# piezo-preamp-tickler_V3-single-supply-OP.net
KiCad netlist of a schematic drawn in EAGLE
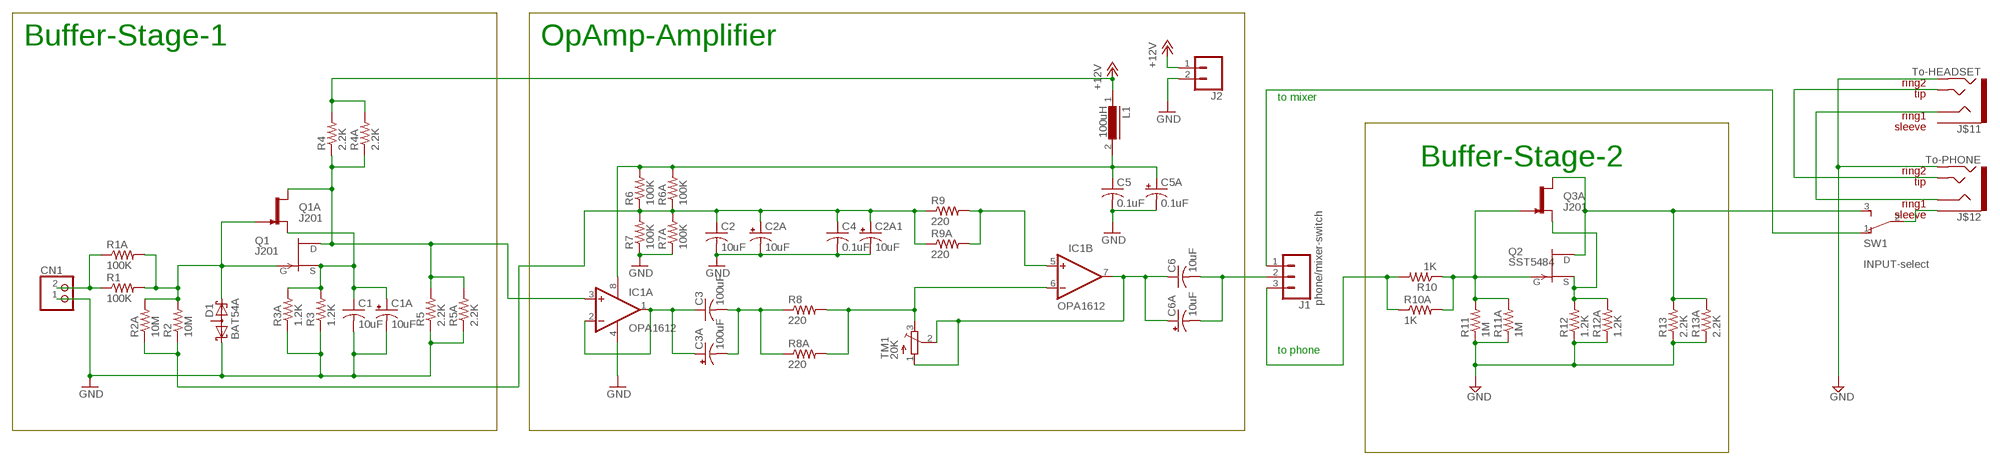
[diagram p0: schematic, sheet 1]
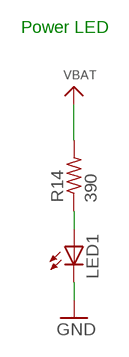
[diagram p1: schematic, sheet 2]

(export (version "E")
  (design (tool "Eeschema 10.0.6"))
  (components
    (comp (ref "C1")
      (value "10uF")
      (footprint "eagle-import:C0805K")
      (libsource (lib "eagle-import") (part "C-USC0805K"))
    )
    (comp (ref "C1A")
      (value "10uF")
      (footprint "eagle-import:E2,5-6E")
      (libsource (lib "eagle-import") (part "CPOL-USE2,5-6E"))
    )
    (comp (ref "C2")
      (value "10uF")
      (footprint "eagle-import:C0805K")
      (libsource (lib "eagle-import") (part "rcl_334_C-USC0805K"))
    )
    (comp (ref "C2A")
      (value "10uF")
      (footprint "eagle-import:E2,5-6E")
      (libsource (lib "eagle-import") (part "CPOL-USE2,5-6E"))
    )
    (comp (ref "C2A1")
      (value "10uF")
      (footprint "eagle-import:E2,5-6E")
      (libsource (lib "eagle-import") (part "CPOL-USE2,5-6E"))
    )
    (comp (ref "C3")
      (value "100uF")
      (footprint "eagle-import:C0805K")
      (libsource (lib "eagle-import") (part "C-USC0805K"))
    )
    (comp (ref "C3A")
      (value "100uF")
      (footprint "eagle-import:E2,5-6E")
      (libsource (lib "eagle-import") (part "CPOL-USE2,5-6E"))
    )
    (comp (ref "C4")
      (value "0.1uF")
      (footprint "eagle-import:C0805K")
      (libsource (lib "eagle-import") (part "C-USC0805K"))
    )
    (comp (ref "C5")
      (value "0.1uF")
      (footprint "eagle-import:C0805K")
      (libsource (lib "eagle-import") (part "C-USC0805K"))
    )
    (comp (ref "C5A")
      (value "0.1uF")
      (footprint "eagle-import:E2,5-6E")
      (libsource (lib "eagle-import") (part "CPOL-USE2,5-6E"))
    )
    (comp (ref "C6")
      (value "10uF")
      (footprint "eagle-import:C0805K")
      (libsource (lib "eagle-import") (part "C-USC0805K"))
    )
    (comp (ref "C6A")
      (value "10uF")
      (footprint "eagle-import:E2,5-6E")
      (libsource (lib "eagle-import") (part "CPOL-USE2,5-6E"))
    )
    (comp (ref "CN1")
      (value "JST_2PIN-THM")
      (footprint "eagle-import:JST-PH-2-THM")
      (libsource (lib "eagle-import") (part "JST_2PIN-THM"))
    )
    (comp (ref "D1")
      (value "BAT54A")
      (footprint "eagle-import:SOT23")
      (libsource (lib "eagle-import") (part "BAT54A"))
    )
    (comp (ref "IC1")
      (value "OPA1612")
      (footprint "eagle-import:SO08")
      (libsource (lib "eagle-import") (part "OPA2UA134"))
    )
    (comp (ref "J$11")
      (value "To-HEADSET")
      (footprint "eagle-import:TRRS-SJ-43514-SMT-TR")
      (libsource (lib "eagle-import") (part "TRRS-3.5MMSJ-43512-SMT"))
    )
    (comp (ref "J$12")
      (value "To-PHONE")
      (footprint "eagle-import:TRRS-SJ-43514-SMT-TR")
      (libsource (lib "eagle-import") (part "TRRS-3.5MMSJ-43512-SMT"))
    )
    (comp (ref "J1")
      (value "phone/mixer-switch")
      (footprint "eagle-import:1X03_LOCK")
      (libsource (lib "eagle-import") (part "CONN_03LOCK"))
    )
    (comp (ref "J2")
      (value "CONN_02LOCK")
      (footprint "eagle-import:1X02_LOCK")
      (libsource (lib "eagle-import") (part "CONN_02LOCK"))
    )
    (comp (ref "L1")
      (value "100uH")
      (footprint "eagle-import:LBC-SE")
      (libsource (lib "eagle-import") (part "LBC-SE"))
    )
    (comp (ref "Q1")
      (value "J201")
      (footprint "eagle-import:SOT23")
      (libsource (lib "eagle-import") (part "?548SST4"))
    )
    (comp (ref "Q1A")
      (value "J201")
      (footprint "eagle-import:TO92-")
      (libsource (lib "eagle-import") (part "J201"))
    )
    (comp (ref "Q2")
      (value "SST5484")
      (footprint "eagle-import:SOT23")
      (libsource (lib "eagle-import") (part "?548SST4"))
    )
    (comp (ref "Q3A")
      (value "J201")
      (footprint "eagle-import:TO92-")
      (libsource (lib "eagle-import") (part "J201"))
    )
    (comp (ref "R1")
      (value "100K")
      (footprint "eagle-import:R0603")
      (libsource (lib "eagle-import") (part "R-US_R0603"))
    )
    (comp (ref "R1A")
      (value "100K")
      (footprint "eagle-import:0204V")
      (libsource (lib "eagle-import") (part "R-US_0204/2V"))
    )
    (comp (ref "R2")
      (value "10M")
      (footprint "eagle-import:R0603")
      (libsource (lib "eagle-import") (part "R-US_R0603"))
    )
    (comp (ref "R2A")
      (value "10M")
      (footprint "eagle-import:0204V")
      (libsource (lib "eagle-import") (part "R-US_0204/2V"))
    )
    (comp (ref "R3")
      (value "1.2K")
      (footprint "eagle-import:R0603")
      (libsource (lib "eagle-import") (part "R-US_R0603"))
    )
    (comp (ref "R3A")
      (value "1.2K")
      (footprint "eagle-import:0204V")
      (libsource (lib "eagle-import") (part "R-US_0204/2V"))
    )
    (comp (ref "R4")
      (value "2.2K")
      (footprint "eagle-import:R0603")
      (libsource (lib "eagle-import") (part "R-US_R0603"))
    )
    (comp (ref "R4A")
      (value "2.2K")
      (footprint "eagle-import:0204V")
      (libsource (lib "eagle-import") (part "R-US_0204/2V"))
    )
    (comp (ref "R5")
      (value "2.2K")
      (footprint "eagle-import:R0603")
      (libsource (lib "eagle-import") (part "R-US_R0603"))
    )
    (comp (ref "R5A")
      (value "2.2K")
      (footprint "eagle-import:0204V")
      (libsource (lib "eagle-import") (part "R-US_0204/2V"))
    )
    (comp (ref "R6")
      (value "100K")
      (footprint "eagle-import:R0603")
      (libsource (lib "eagle-import") (part "R-US_R0603"))
    )
    (comp (ref "R6A")
      (value "100K")
      (footprint "eagle-import:0204V")
      (libsource (lib "eagle-import") (part "R-US_0204/2V"))
    )
    (comp (ref "R7")
      (value "100K")
      (footprint "eagle-import:R0603")
      (libsource (lib "eagle-import") (part "R-US_R0603"))
    )
    (comp (ref "R7A")
      (value "100K")
      (footprint "eagle-import:0204V")
      (libsource (lib "eagle-import") (part "R-US_0204/2V"))
    )
    (comp (ref "R8")
      (value "220")
      (footprint "eagle-import:R0603")
      (libsource (lib "eagle-import") (part "R-US_R0603"))
    )
    (comp (ref "R8A")
      (value "220")
      (footprint "eagle-import:R0603")
      (libsource (lib "eagle-import") (part "R-US_R0603"))
    )
    (comp (ref "R9")
      (value "220")
      (footprint "eagle-import:R0603")
      (libsource (lib "eagle-import") (part "R-US_R0603"))
    )
    (comp (ref "R9A")
      (value "220")
      (footprint "eagle-import:0204V")
      (libsource (lib "eagle-import") (part "R-US_0204/2V"))
    )
    (comp (ref "R10")
      (value "1K")
      (footprint "eagle-import:R0603")
      (libsource (lib "eagle-import") (part "R-US_R0603"))
    )
    (comp (ref "R10A")
      (value "1K")
      (footprint "eagle-import:0204V")
      (libsource (lib "eagle-import") (part "R-US_0204/2V"))
    )
    (comp (ref "R11")
      (value "1M")
      (footprint "eagle-import:R0603")
      (libsource (lib "eagle-import") (part "R-US_R0603"))
    )
    (comp (ref "R11A")
      (value "1M")
      (footprint "eagle-import:0204V")
      (libsource (lib "eagle-import") (part "R-US_0204/2V"))
    )
    (comp (ref "R12")
      (value "1.2K")
      (footprint "eagle-import:R0603")
      (libsource (lib "eagle-import") (part "R-US_R0603"))
    )
    (comp (ref "R12A")
      (value "1.2K")
      (footprint "eagle-import:0204V")
      (libsource (lib "eagle-import") (part "R-US_0204/2V"))
    )
    (comp (ref "R13")
      (value "2.2K")
      (footprint "eagle-import:R0603")
      (libsource (lib "eagle-import") (part "R-US_R0603"))
    )
    (comp (ref "R13A")
      (value "2.2K")
      (footprint "eagle-import:0204V")
      (libsource (lib "eagle-import") (part "R-US_0204/2V"))
    )
    (comp (ref "SW1")
      (value "INPUT-select")
      (footprint "eagle-import:SWITCH_SPDT-TE-CONNECT")
      (libsource (lib "eagle-import") (part "SWITCH_SPDTTE-CONNECT"))
    )
    (comp (ref "TM1")
      (value "20K")
      (footprint "eagle-import:TC33X")
      (libsource (lib "eagle-import") (part "TRIMPOTTC33X"))
    )
    (comp (ref "LED1")
      (value "LED3MM")
      (footprint "eagle-import:LED3MM")
      (libsource (lib "eagle-import") (part "LED3MM"))
    )
    (comp (ref "R14")
      (value "390")
      (footprint "eagle-import:R0805")
      (libsource (lib "eagle-import") (part "R-US_R0805"))
    )
  )
  (nets
    (net (code "1") (name "+12V") (class "Default")
      (node (ref "J2") (pin "1") (pinfunction "1_1") (pintype "passive"))
      (node (ref "L1") (pin "1") (pinfunction "1_1") (pintype "passive"))
      (node (ref "R4") (pin "2") (pinfunction "2_2") (pintype "passive"))
      (node (ref "R4A") (pin "2") (pinfunction "2_2") (pintype "passive"))
    )
    (net (code "2") (name "GND") (class "Default")
      (node (ref "C1") (pin "2") (pinfunction "2_2") (pintype "passive"))
      (node (ref "C1A") (pin "-") (pinfunction "-_-") (pintype "passive"))
      (node (ref "C2") (pin "2") (pinfunction "2_2") (pintype "passive"))
      (node (ref "C2A") (pin "-") (pinfunction "-_-") (pintype "passive"))
      (node (ref "C2A1") (pin "-") (pinfunction "-_-") (pintype "passive"))
      (node (ref "C4") (pin "2") (pinfunction "2_2") (pintype "passive"))
      (node (ref "C5") (pin "2") (pinfunction "2_2") (pintype "passive"))
      (node (ref "C5A") (pin "-") (pinfunction "-_-") (pintype "passive"))
      (node (ref "CN1") (pin "1") (pinfunction "2_1") (pintype "passive"))
      (node (ref "D1") (pin "1") (pinfunction "K1_1") (pintype "passive"))
      (node (ref "IC1") (pin "4") (pinfunction "V-_4") (pintype "power_in"))
      (node (ref "J$11") (pin "4") (pinfunction "RING2_4") (pintype "bidirectional"))
      (node (ref "J$12") (pin "4") (pinfunction "RING2_4") (pintype "bidirectional"))
      (node (ref "J2") (pin "2") (pinfunction "2_2") (pintype "passive"))
      (node (ref "LED1") (pin "K") (pinfunction "C_K") (pintype "passive"))
      (node (ref "R11") (pin "1") (pinfunction "1_1") (pintype "passive"))
      (node (ref "R11A") (pin "1") (pinfunction "1_1") (pintype "passive"))
      (node (ref "R12") (pin "1") (pinfunction "1_1") (pintype "passive"))
      (node (ref "R12A") (pin "1") (pinfunction "1_1") (pintype "passive"))
      (node (ref "R13") (pin "1") (pinfunction "1_1") (pintype "passive"))
      (node (ref "R13A") (pin "1") (pinfunction "1_1") (pintype "passive"))
      (node (ref "R3") (pin "1") (pinfunction "1_1") (pintype "passive"))
      (node (ref "R3A") (pin "1") (pinfunction "1_1") (pintype "passive"))
      (node (ref "R5") (pin "1") (pinfunction "1_1") (pintype "passive"))
      (node (ref "R5A") (pin "1") (pinfunction "1_1") (pintype "passive"))
      (node (ref "R7") (pin "1") (pinfunction "1_1") (pintype "passive"))
      (node (ref "R7A") (pin "1") (pinfunction "1_1") (pintype "passive"))
    )
    (net (code "3") (name "Net-(C2-Pad1)") (class "Default")
      (node (ref "C2") (pin "1") (pinfunction "1_1") (pintype "passive"))
      (node (ref "C2A") (pin "+") (pinfunction "+_+") (pintype "passive"))
      (node (ref "C2A1") (pin "+") (pinfunction "+_+") (pintype "passive"))
      (node (ref "C4") (pin "1") (pinfunction "1_1") (pintype "passive"))
      (node (ref "R2") (pin "1") (pinfunction "1_1") (pintype "passive"))
      (node (ref "R2A") (pin "1") (pinfunction "1_1") (pintype "passive"))
      (node (ref "R6") (pin "1") (pinfunction "1_1") (pintype "passive"))
      (node (ref "R6A") (pin "1") (pinfunction "1_1") (pintype "passive"))
      (node (ref "R7") (pin "2") (pinfunction "2_2") (pintype "passive"))
      (node (ref "R7A") (pin "2") (pinfunction "2_2") (pintype "passive"))
      (node (ref "R9") (pin "1") (pinfunction "1_1") (pintype "passive"))
      (node (ref "R9A") (pin "1") (pinfunction "1_1") (pintype "passive"))
    )
    (net (code "4") (name "Net-(C3-Pad2)") (class "Default")
      (node (ref "C3") (pin "2") (pinfunction "2_2") (pintype "passive"))
      (node (ref "C3A") (pin "-") (pinfunction "-_-") (pintype "passive"))
      (node (ref "R8") (pin "1") (pinfunction "1_1") (pintype "passive"))
      (node (ref "R8A") (pin "1") (pinfunction "1_1") (pintype "passive"))
    )
    (net (code "5") (name "Net-(C6-Pad2)") (class "Default")
      (node (ref "C6") (pin "2") (pinfunction "2_2") (pintype "passive"))
      (node (ref "C6A") (pin "-") (pinfunction "-_-") (pintype "passive"))
      (node (ref "J1") (pin "2") (pinfunction "2_2") (pintype "passive"))
    )
    (net (code "6") (name "Net-(CN1-1)") (class "Default")
      (node (ref "CN1") (pin "2") (pinfunction "1_2") (pintype "passive"))
      (node (ref "R1") (pin "1") (pinfunction "1_1") (pintype "passive"))
      (node (ref "R1A") (pin "1") (pinfunction "1_1") (pintype "passive"))
    )
    (net (code "7") (name "Net-(D1-K2)") (class "Default")
      (node (ref "D1") (pin "2") (pinfunction "K2_2") (pintype "passive"))
      (node (ref "Q1") (pin "3") (pinfunction "G_3") (pintype "passive"))
      (node (ref "Q1A") (pin "1") (pinfunction "G_1") (pintype "passive"))
      (node (ref "R1") (pin "2") (pinfunction "2_2") (pintype "passive"))
      (node (ref "R1A") (pin "2") (pinfunction "2_2") (pintype "passive"))
      (node (ref "R2") (pin "2") (pinfunction "2_2") (pintype "passive"))
      (node (ref "R2A") (pin "2") (pinfunction "2_2") (pintype "passive"))
    )
    (net (code "8") (name "Net-(IC1A-+IN)") (class "Default")
      (node (ref "IC1") (pin "3") (pinfunction "+IN_3") (pintype "input"))
      (node (ref "Q1") (pin "1") (pinfunction "D_1") (pintype "passive"))
      (node (ref "Q1A") (pin "3") (pinfunction "D_3") (pintype "passive"))
      (node (ref "R4") (pin "1") (pinfunction "1_1") (pintype "passive"))
      (node (ref "R4A") (pin "1") (pinfunction "1_1") (pintype "passive"))
      (node (ref "R5") (pin "2") (pinfunction "2_2") (pintype "passive"))
      (node (ref "R5A") (pin "2") (pinfunction "2_2") (pintype "passive"))
    )
    (net (code "9") (name "Net-(IC1A--IN)") (class "Default")
      (node (ref "C3") (pin "1") (pinfunction "1_1") (pintype "passive"))
      (node (ref "C3A") (pin "+") (pinfunction "+_+") (pintype "passive"))
      (node (ref "IC1") (pin "1") (pinfunction "OUT_1") (pintype "output"))
      (node (ref "IC1") (pin "2") (pinfunction "-IN_2") (pintype "input"))
    )
    (net (code "10") (name "Net-(IC1A-V+)") (class "Default")
      (node (ref "C5") (pin "1") (pinfunction "1_1") (pintype "passive"))
      (node (ref "C5A") (pin "+") (pinfunction "+_+") (pintype "passive"))
      (node (ref "IC1") (pin "8") (pinfunction "V+_8") (pintype "power_in"))
      (node (ref "L1") (pin "2") (pinfunction "2_2") (pintype "passive"))
      (node (ref "R6") (pin "2") (pinfunction "2_2") (pintype "passive"))
      (node (ref "R6A") (pin "2") (pinfunction "2_2") (pintype "passive"))
    )
    (net (code "11") (name "Net-(IC1B-+IN)") (class "Default")
      (node (ref "IC1") (pin "5") (pinfunction "+IN_5") (pintype "input"))
      (node (ref "R9") (pin "2") (pinfunction "2_2") (pintype "passive"))
      (node (ref "R9A") (pin "2") (pinfunction "2_2") (pintype "passive"))
    )
    (net (code "12") (name "Net-(IC1B--IN)") (class "Default")
      (node (ref "IC1") (pin "6") (pinfunction "-IN_6") (pintype "input"))
      (node (ref "R8") (pin "2") (pinfunction "2_2") (pintype "passive"))
      (node (ref "R8A") (pin "2") (pinfunction "2_2") (pintype "passive"))
      (node (ref "TM1") (pin "3") (pinfunction "E_3") (pintype "passive"))
    )
    (net (code "13") (name "Net-(IC1B-OUT)") (class "Default")
      (node (ref "C6") (pin "1") (pinfunction "1_1") (pintype "passive"))
      (node (ref "C6A") (pin "+") (pinfunction "+_+") (pintype "passive"))
      (node (ref "IC1") (pin "7") (pinfunction "OUT_7") (pintype "output"))
      (node (ref "TM1") (pin "1") (pinfunction "A_1") (pintype "passive"))
      (node (ref "TM1") (pin "2") (pinfunction "S_2") (pintype "passive"))
    )
    (net (code "14") (name "Net-(J$11-RING1)") (class "Default")
      (node (ref "J$11") (pin "3") (pinfunction "RING1_3") (pintype "bidirectional"))
      (node (ref "J$12") (pin "3") (pinfunction "RING1_3") (pintype "bidirectional"))
    )
    (net (code "15") (name "Net-(J$11-TIP)") (class "Default")
      (node (ref "J$11") (pin "2") (pinfunction "TIP_2") (pintype "bidirectional"))
      (node (ref "J$12") (pin "2") (pinfunction "TIP_2") (pintype "bidirectional"))
    )
    (net (code "16") (name "Net-(J$12-EARTH)") (class "Default")
      (node (ref "J$12") (pin "1") (pinfunction "EARTH_1") (pintype "bidirectional"))
      (node (ref "SW1") (pin "2") (pinfunction "2_2") (pintype "passive"))
    )
    (net (code "17") (name "Net-(J1-Pad1)") (class "Default")
      (node (ref "J1") (pin "1") (pinfunction "1_1") (pintype "passive"))
      (node (ref "SW1") (pin "1") (pinfunction "1_1") (pintype "passive"))
    )
    (net (code "18") (name "Net-(J1-Pad3)") (class "Default")
      (node (ref "J1") (pin "3") (pinfunction "3_3") (pintype "passive"))
      (node (ref "R10") (pin "2") (pinfunction "2_2") (pintype "passive"))
      (node (ref "R10A") (pin "1") (pinfunction "1_1") (pintype "passive"))
    )
    (net (code "19") (name "Net-(LED1-PadA)") (class "Default")
      (node (ref "LED1") (pin "A") (pinfunction "A_A") (pintype "passive"))
      (node (ref "R14") (pin "1") (pinfunction "1_1") (pintype "passive"))
    )
    (net (code "20") (name "Net-(Q1-S)") (class "Default")
      (node (ref "C1") (pin "1") (pinfunction "1_1") (pintype "passive"))
      (node (ref "C1A") (pin "+") (pinfunction "+_+") (pintype "passive"))
      (node (ref "Q1") (pin "2") (pinfunction "S_2") (pintype "passive"))
      (node (ref "Q1A") (pin "2") (pinfunction "S_2") (pintype "passive"))
      (node (ref "R3") (pin "2") (pinfunction "2_2") (pintype "passive"))
      (node (ref "R3A") (pin "2") (pinfunction "2_2") (pintype "passive"))
    )
    (net (code "21") (name "Net-(Q2-D)") (class "Default")
      (node (ref "Q2") (pin "1") (pinfunction "D_1") (pintype "passive"))
      (node (ref "Q3A") (pin "3") (pinfunction "D_3") (pintype "passive"))
      (node (ref "R13") (pin "2") (pinfunction "2_2") (pintype "passive"))
      (node (ref "R13A") (pin "2") (pinfunction "2_2") (pintype "passive"))
      (node (ref "SW1") (pin "3") (pinfunction "3_3") (pintype "passive"))
    )
    (net (code "22") (name "Net-(Q2-G)") (class "Default")
      (node (ref "Q2") (pin "3") (pinfunction "G_3") (pintype "passive"))
      (node (ref "Q3A") (pin "1") (pinfunction "G_1") (pintype "passive"))
      (node (ref "R10") (pin "1") (pinfunction "1_1") (pintype "passive"))
      (node (ref "R10A") (pin "2") (pinfunction "2_2") (pintype "passive"))
      (node (ref "R11") (pin "2") (pinfunction "2_2") (pintype "passive"))
      (node (ref "R11A") (pin "2") (pinfunction "2_2") (pintype "passive"))
    )
    (net (code "23") (name "Net-(Q2-S)") (class "Default")
      (node (ref "Q2") (pin "2") (pinfunction "S_2") (pintype "passive"))
      (node (ref "Q3A") (pin "2") (pinfunction "S_2") (pintype "passive"))
      (node (ref "R12") (pin "2") (pinfunction "2_2") (pintype "passive"))
      (node (ref "R12A") (pin "2") (pinfunction "2_2") (pintype "passive"))
    )
    (net (code "24") (name "VBAT") (class "Default")
      (node (ref "R14") (pin "2") (pinfunction "2_2") (pintype "passive"))
    )
    (net (code "25") (name "unconnected-(D1-AA-Pad3)") (class "Default")
      (node (ref "D1") (pin "3") (pinfunction "AA_3") (pintype "passive"))
    )
    (net (code "26") (name "unconnected-(J$11-EARTH-Pad1)") (class "Default")
      (node (ref "J$11") (pin "1") (pinfunction "EARTH_1") (pintype "bidirectional"))
    )
  )
)
